# ihc_mon_orig.net
KiCad netlist of a schematic drawn in EAGLE
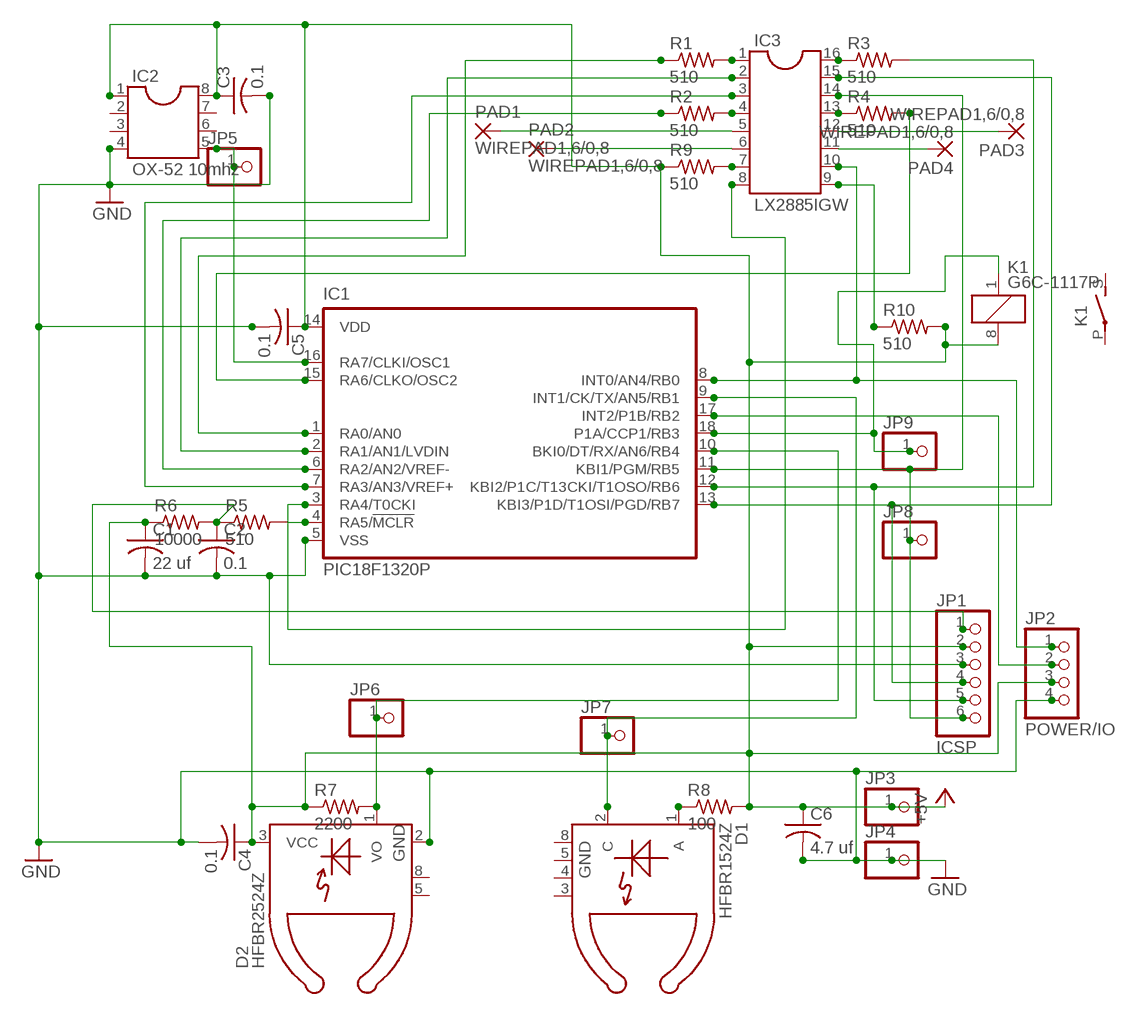
[diagram p0: schematic, sheet 1]

(export (version "E")
  (design (tool "Eeschema 10.0.6"))
  (components
    (comp (ref "C1")
      (value "22 uf")
      (footprint "eagle-import:C025-024X044")
      (libsource (lib "eagle-import") (part "C-US025-024X044"))
    )
    (comp (ref "C2")
      (value "0.1")
      (footprint "eagle-import:C050-025X075")
      (libsource (lib "eagle-import") (part "C-US050-025X075"))
    )
    (comp (ref "C3")
      (value "0.1")
      (footprint "eagle-import:C050-025X075")
      (libsource (lib "eagle-import") (part "C-US050-025X075"))
    )
    (comp (ref "C4")
      (value "0.1")
      (footprint "eagle-import:C050-025X075")
      (libsource (lib "eagle-import") (part "C-US050-025X075"))
    )
    (comp (ref "C5")
      (value "0.1")
      (footprint "eagle-import:C050-025X075")
      (libsource (lib "eagle-import") (part "C-US050-025X075"))
    )
    (comp (ref "C6")
      (value "4.7 uf")
      (footprint "eagle-import:C025-024X044")
      (libsource (lib "eagle-import") (part "C-US025-024X044"))
    )
    (comp (ref "D1")
      (value "HFBR1524Z")
      (footprint "eagle-import:HFBR25XX")
      (fields (field (name "MF") "AGILENT TECHNOLOGIES") (field (name "MPN") "HFBR-1528"))
      (libsource (lib "eagle-import") (part "HFBR1528"))
    )
    (comp (ref "D2")
      (value "HFBR2524Z")
      (footprint "eagle-import:HFBR25XX")
      (fields (field (name "MF") "AGILENT TECHNOLOGIES") (field (name "MPN") "HFBR-2528"))
      (libsource (lib "eagle-import") (part "HFBR2528"))
    )
    (comp (ref "IC1")
      (value "PIC18F1320P")
      (footprint "eagle-import:DIL18")
      (fields (field (name "MF") "MICROCHIP") (field (name "MPN") "PIC18F1320-I/P"))
      (libsource (lib "eagle-import") (part "PIC18F120P2"))
    )
    (comp (ref "IC2")
      (value "OX-52 10mhz")
      (footprint "eagle-import:SOCKET-08")
      (libsource (lib "eagle-import") (part "DIL8S"))
    )
    (comp (ref "IC3")
      (value "LX2885IGW")
      (footprint "eagle-import:SOCKET-16")
      (libsource (lib "eagle-import") (part "DIL16S"))
    )
    (comp (ref "JP1")
      (value "ICSP")
      (footprint "eagle-import:1X06")
      (libsource (lib "eagle-import") (part "PINHD-1X6"))
    )
    (comp (ref "JP2")
      (value "POWER/IO")
      (footprint "eagle-import:1X04")
      (libsource (lib "eagle-import") (part "PINHD-1X4"))
    )
    (comp (ref "JP3")
      (value "PINHD-1X1")
      (footprint "eagle-import:1X01")
      (libsource (lib "eagle-import") (part "PINHD-1X1"))
    )
    (comp (ref "JP4")
      (value "PINHD-1X1")
      (footprint "eagle-import:1X01")
      (libsource (lib "eagle-import") (part "PINHD-1X1"))
    )
    (comp (ref "JP5")
      (value "PINHD-1X1")
      (footprint "eagle-import:1X01")
      (libsource (lib "eagle-import") (part "PINHD-1X1"))
    )
    (comp (ref "JP6")
      (value "PINHD-1X1")
      (footprint "eagle-import:1X01")
      (libsource (lib "eagle-import") (part "PINHD-1X1"))
    )
    (comp (ref "JP7")
      (value "PINHD-1X1")
      (footprint "eagle-import:1X01")
      (libsource (lib "eagle-import") (part "PINHD-1X1"))
    )
    (comp (ref "JP8")
      (value "PINHD-1X1")
      (footprint "eagle-import:1X01")
      (libsource (lib "eagle-import") (part "PINHD-1X1"))
    )
    (comp (ref "JP9")
      (value "PINHD-1X1")
      (footprint "eagle-import:1X01")
      (libsource (lib "eagle-import") (part "PINHD-1X1"))
    )
    (comp (ref "K1")
      (value "G6C-1117P")
      (footprint "eagle-import:G6C-1117P")
      (libsource (lib "eagle-import") (part "G6C-1117P"))
    )
    (comp (ref "PAD1")
      (value "WIREPAD1,6/0,8")
      (footprint "eagle-import:1,6_0,8")
      (libsource (lib "eagle-import") (part "WIREPAD1,6/0,8"))
    )
    (comp (ref "PAD2")
      (value "WIREPAD1,6/0,8")
      (footprint "eagle-import:1,6_0,8")
      (libsource (lib "eagle-import") (part "WIREPAD1,6/0,8"))
    )
    (comp (ref "PAD3")
      (value "WIREPAD1,6/0,8")
      (footprint "eagle-import:1,6_0,8")
      (libsource (lib "eagle-import") (part "WIREPAD1,6/0,8"))
    )
    (comp (ref "PAD4")
      (value "WIREPAD1,6/0,8")
      (footprint "eagle-import:1,6_0,8")
      (libsource (lib "eagle-import") (part "WIREPAD1,6/0,8"))
    )
    (comp (ref "R1")
      (value "510")
      (footprint "eagle-import:0204V")
      (libsource (lib "eagle-import") (part "R-US_0204/2V"))
    )
    (comp (ref "R2")
      (value "510")
      (footprint "eagle-import:0204V")
      (libsource (lib "eagle-import") (part "R-US_0204/2V"))
    )
    (comp (ref "R3")
      (value "510")
      (footprint "eagle-import:0204V")
      (libsource (lib "eagle-import") (part "R-US_0204/2V"))
    )
    (comp (ref "R4")
      (value "510")
      (footprint "eagle-import:0204V")
      (libsource (lib "eagle-import") (part "R-US_0204/2V"))
    )
    (comp (ref "R5")
      (value "510")
      (footprint "eagle-import:0204V")
      (libsource (lib "eagle-import") (part "R-US_0204/2V"))
    )
    (comp (ref "R6")
      (value "10000")
      (footprint "eagle-import:0204V")
      (libsource (lib "eagle-import") (part "R-US_0204/2V"))
    )
    (comp (ref "R7")
      (value "2200")
      (footprint "eagle-import:0204V")
      (libsource (lib "eagle-import") (part "R-US_0204/2V"))
    )
    (comp (ref "R8")
      (value "100")
      (footprint "eagle-import:0204V")
      (libsource (lib "eagle-import") (part "R-US_0204/2V"))
    )
    (comp (ref "R9")
      (value "510")
      (footprint "eagle-import:0204V")
      (libsource (lib "eagle-import") (part "R-US_0204/2V"))
    )
    (comp (ref "R10")
      (value "510")
      (footprint "eagle-import:0204V")
      (libsource (lib "eagle-import") (part "R-US_0204/2V"))
    )
  )
  (nets
    (net (code "1") (name "+5V") (class "Default")
      (node (ref "C1") (pin "1") (pinfunction "1_1") (pintype "passive"))
      (node (ref "C3") (pin "1") (pinfunction "1_1") (pintype "passive"))
      (node (ref "C4") (pin "1") (pinfunction "1_1") (pintype "passive"))
      (node (ref "C5") (pin "1") (pinfunction "1_1") (pintype "passive"))
      (node (ref "C6") (pin "1") (pinfunction "1_1") (pintype "passive"))
      (node (ref "D2") (pin "3") (pinfunction "VCC_3") (pintype "passive"))
      (node (ref "IC1") (pin "14") (pinfunction "VDD_14") (pintype "power_in"))
      (node (ref "IC2") (pin "1") (pinfunction "1_1") (pintype "passive"))
      (node (ref "IC2") (pin "8") (pinfunction "8_8") (pintype "passive"))
      (node (ref "JP1") (pin "2") (pinfunction "2_2") (pintype "passive"))
      (node (ref "JP2") (pin "3") (pinfunction "3_3") (pintype "passive"))
      (node (ref "JP3") (pin "1") (pinfunction "1_1") (pintype "passive"))
      (node (ref "K1") (pin "8") (pinfunction "2_8") (pintype "passive"))
      (node (ref "R10") (pin "2") (pinfunction "2_2") (pintype "passive"))
      (node (ref "R6") (pin "1") (pinfunction "1_1") (pintype "passive"))
      (node (ref "R7") (pin "1") (pinfunction "1_1") (pintype "passive"))
      (node (ref "R8") (pin "2") (pinfunction "2_2") (pintype "passive"))
      (node (ref "R9") (pin "1") (pinfunction "1_1") (pintype "passive"))
    )
    (net (code "2") (name "GND") (class "Default")
      (node (ref "C1") (pin "2") (pinfunction "2_2") (pintype "passive"))
      (node (ref "C2") (pin "2") (pinfunction "2_2") (pintype "passive"))
      (node (ref "C3") (pin "2") (pinfunction "2_2") (pintype "passive"))
      (node (ref "C4") (pin "2") (pinfunction "2_2") (pintype "passive"))
      (node (ref "C5") (pin "2") (pinfunction "2_2") (pintype "passive"))
      (node (ref "C6") (pin "2") (pinfunction "2_2") (pintype "passive"))
      (node (ref "D2") (pin "2") (pinfunction "GND_2") (pintype "passive"))
      (node (ref "IC1") (pin "5") (pinfunction "VSS_5") (pintype "power_in"))
      (node (ref "IC2") (pin "4") (pinfunction "4_4") (pintype "passive"))
      (node (ref "JP1") (pin "3") (pinfunction "3_3") (pintype "passive"))
      (node (ref "JP2") (pin "4") (pinfunction "4_4") (pintype "passive"))
      (node (ref "JP4") (pin "1") (pinfunction "1_1") (pintype "passive"))
    )
    (net (code "3") (name "Net-(C2-Pad1)") (class "Default")
      (node (ref "C2") (pin "1") (pinfunction "1_1") (pintype "passive"))
      (node (ref "JP1") (pin "1") (pinfunction "1_1") (pintype "passive"))
      (node (ref "R5") (pin "1") (pinfunction "1_1") (pintype "passive"))
      (node (ref "R6") (pin "2") (pinfunction "2_2") (pintype "passive"))
    )
    (net (code "4") (name "Net-(D1-A)") (class "Default")
      (node (ref "D1") (pin "1") (pinfunction "A_1") (pintype "passive"))
      (node (ref "R8") (pin "1") (pinfunction "1_1") (pintype "passive"))
    )
    (net (code "5") (name "Net-(D1-C)") (class "Default")
      (node (ref "D1") (pin "2") (pinfunction "C_2") (pintype "passive"))
      (node (ref "IC1") (pin "9") (pinfunction "INT1/CK/TX/AN5/RB1_9") (pintype "bidirectional"))
      (node (ref "JP7") (pin "1") (pinfunction "1_1") (pintype "passive"))
    )
    (net (code "6") (name "Net-(D2-VO)") (class "Default")
      (node (ref "D2") (pin "1") (pinfunction "VO_1") (pintype "output"))
      (node (ref "IC1") (pin "10") (pinfunction "BKI0/DT/RX/AN6/RB4_10") (pintype "bidirectional"))
      (node (ref "JP6") (pin "1") (pinfunction "1_1") (pintype "passive"))
      (node (ref "R7") (pin "2") (pinfunction "2_2") (pintype "passive"))
    )
    (net (code "7") (name "Net-(IC1-INT0{slash}AN4{slash}RB0)") (class "Default")
      (node (ref "IC1") (pin "8") (pinfunction "INT0/AN4/RB0_8") (pintype "bidirectional"))
      (node (ref "IC3") (pin "10") (pinfunction "10_10") (pintype "passive"))
      (node (ref "JP2") (pin "1") (pinfunction "1_1") (pintype "passive"))
    )
    (net (code "8") (name "Net-(IC1-INT2{slash}P1B{slash}RB2)") (class "Default")
      (node (ref "IC1") (pin "17") (pinfunction "INT2/P1B/RB2_17") (pintype "bidirectional"))
      (node (ref "JP2") (pin "2") (pinfunction "2_2") (pintype "passive"))
    )
    (net (code "9") (name "Net-(IC1-KBI1{slash}PGM{slash}RB5)") (class "Default")
      (node (ref "IC1") (pin "11") (pinfunction "KBI1/PGM/RB5_11") (pintype "bidirectional"))
      (node (ref "IC3") (pin "14") (pinfunction "14_14") (pintype "passive"))
      (node (ref "JP1") (pin "6") (pinfunction "6_6") (pintype "passive"))
      (node (ref "JP8") (pin "1") (pinfunction "1_1") (pintype "passive"))
    )
    (net (code "10") (name "Net-(IC1-KBI2{slash}P1C{slash}T13CKI{slash}T1OSO{slash}RB6)") (class "Default")
      (node (ref "IC1") (pin "12") (pinfunction "KBI2/P1C/T13CKI/T1OSO/RB6_12") (pintype "bidirectional"))
      (node (ref "JP1") (pin "5") (pinfunction "5_5") (pintype "passive"))
      (node (ref "R3") (pin "2") (pinfunction "2_2") (pintype "passive"))
    )
    (net (code "11") (name "Net-(IC1-KBI3{slash}P1D{slash}T1OSI{slash}PGD{slash}RB7)") (class "Default")
      (node (ref "IC1") (pin "13") (pinfunction "KBI3/P1D/T1OSI/PGD/RB7_13") (pintype "bidirectional"))
      (node (ref "IC3") (pin "15") (pinfunction "15_15") (pintype "passive"))
      (node (ref "JP1") (pin "4") (pinfunction "4_4") (pintype "passive"))
    )
    (net (code "12") (name "Net-(IC1-P1A{slash}CCP1{slash}RB3)") (class "Default")
      (node (ref "IC1") (pin "18") (pinfunction "P1A/CCP1/RB3_18") (pintype "bidirectional"))
      (node (ref "JP9") (pin "1") (pinfunction "1_1") (pintype "passive"))
      (node (ref "K1") (pin "1") (pinfunction "1_1") (pintype "passive"))
    )
    (net (code "13") (name "Net-(IC1-RA0{slash}AN0)") (class "Default")
      (node (ref "IC1") (pin "1") (pinfunction "RA0/AN0_1") (pintype "bidirectional"))
      (node (ref "R1") (pin "1") (pinfunction "1_1") (pintype "passive"))
    )
    (net (code "14") (name "Net-(IC1-RA1{slash}AN1{slash}LVDIN)") (class "Default")
      (node (ref "IC1") (pin "2") (pinfunction "RA1/AN1/LVDIN_2") (pintype "bidirectional"))
      (node (ref "IC3") (pin "2") (pinfunction "2_2") (pintype "passive"))
    )
    (net (code "15") (name "Net-(IC1-RA2{slash}AN2{slash}VREF-)") (class "Default")
      (node (ref "IC1") (pin "6") (pinfunction "RA2/AN2/VREF-_6") (pintype "bidirectional"))
      (node (ref "R2") (pin "1") (pinfunction "1_1") (pintype "passive"))
    )
    (net (code "16") (name "Net-(IC1-RA3{slash}AN3{slash}VREF+)") (class "Default")
      (node (ref "IC1") (pin "7") (pinfunction "RA3/AN3/VREF+_7") (pintype "bidirectional"))
      (node (ref "IC3") (pin "3") (pinfunction "3_3") (pintype "passive"))
    )
    (net (code "17") (name "Net-(IC1-RA4{slash}T0CKI)") (class "Default")
      (node (ref "IC1") (pin "3") (pinfunction "RA4/T0CKI_3") (pintype "bidirectional"))
      (node (ref "IC3") (pin "8") (pinfunction "8_8") (pintype "passive"))
    )
    (net (code "18") (name "Net-(IC1-RA5{slash}~{MCLR})") (class "Default")
      (node (ref "IC1") (pin "4") (pinfunction "RA5/~{MCLR}_4") (pintype "input"))
      (node (ref "R5") (pin "2") (pinfunction "2_2") (pintype "passive"))
    )
    (net (code "19") (name "Net-(IC1-RA6{slash}CLKO{slash}OSC2)") (class "Default")
      (node (ref "IC1") (pin "15") (pinfunction "RA6/CLKO/OSC2_15") (pintype "bidirectional"))
      (node (ref "R4") (pin "2") (pinfunction "2_2") (pintype "passive"))
    )
    (net (code "20") (name "Net-(IC1-RA7{slash}CLKI{slash}OSC1)") (class "Default")
      (node (ref "IC1") (pin "16") (pinfunction "RA7/CLKI/OSC1_16") (pintype "bidirectional"))
      (node (ref "IC2") (pin "5") (pinfunction "5_5") (pintype "passive"))
      (node (ref "JP5") (pin "1") (pinfunction "1_1") (pintype "passive"))
    )
    (net (code "21") (name "Net-(IC3-Pad1)") (class "Default")
      (node (ref "IC3") (pin "1") (pinfunction "1_1") (pintype "passive"))
      (node (ref "R1") (pin "2") (pinfunction "2_2") (pintype "passive"))
    )
    (net (code "22") (name "Net-(IC3-Pad4)") (class "Default")
      (node (ref "IC3") (pin "4") (pinfunction "4_4") (pintype "passive"))
      (node (ref "R2") (pin "2") (pinfunction "2_2") (pintype "passive"))
    )
    (net (code "23") (name "Net-(IC3-Pad7)") (class "Default")
      (node (ref "IC3") (pin "7") (pinfunction "7_7") (pintype "passive"))
      (node (ref "R9") (pin "2") (pinfunction "2_2") (pintype "passive"))
    )
    (net (code "24") (name "Net-(IC3-Pad9)") (class "Default")
      (node (ref "IC3") (pin "9") (pinfunction "9_9") (pintype "passive"))
      (node (ref "R10") (pin "1") (pinfunction "1_1") (pintype "passive"))
    )
    (net (code "25") (name "Net-(IC3-Pad13)") (class "Default")
      (node (ref "IC3") (pin "13") (pinfunction "13_13") (pintype "passive"))
      (node (ref "R4") (pin "1") (pinfunction "1_1") (pintype "passive"))
    )
    (net (code "26") (name "Net-(IC3-Pad16)") (class "Default")
      (node (ref "IC3") (pin "16") (pinfunction "16_16") (pintype "passive"))
      (node (ref "R3") (pin "1") (pinfunction "1_1") (pintype "passive"))
    )
    (net (code "27") (name "Net-(PAD1-P)") (class "Default")
      (node (ref "IC3") (pin "5") (pinfunction "5_5") (pintype "passive"))
      (node (ref "PAD1") (pin "1") (pinfunction "P_1") (pintype "passive"))
    )
    (net (code "28") (name "Net-(PAD2-P)") (class "Default")
      (node (ref "IC3") (pin "6") (pinfunction "6_6") (pintype "passive"))
      (node (ref "PAD2") (pin "1") (pinfunction "P_1") (pintype "passive"))
    )
    (net (code "29") (name "Net-(PAD3-P)") (class "Default")
      (node (ref "IC3") (pin "12") (pinfunction "12_12") (pintype "passive"))
      (node (ref "PAD3") (pin "1") (pinfunction "P_1") (pintype "passive"))
    )
    (net (code "30") (name "Net-(PAD4-P)") (class "Default")
      (node (ref "IC3") (pin "11") (pinfunction "11_11") (pintype "passive"))
      (node (ref "PAD4") (pin "1") (pinfunction "P_1") (pintype "passive"))
    )
    (net (code "31") (name "unconnected-(D1-1-Pad3)") (class "Default")
      (node (ref "D1") (pin "3") (pinfunction "1_3") (pintype "passive"))
    )
    (net (code "32") (name "unconnected-(D1-GND-Pad5)") (class "Default")
      (node (ref "D1") (pin "5") (pinfunction "GND_5") (pintype "passive"))
    )
    (net (code "33") (name "unconnected-(D1-GND-Pad8)") (class "Default")
      (node (ref "D1") (pin "8") (pinfunction "GND_8") (pintype "passive"))
    )
    (net (code "34") (name "unconnected-(D1-Pad4)") (class "Default")
      (node (ref "D1") (pin "4") (pinfunction "4_4") (pintype "passive"))
    )
    (net (code "35") (name "unconnected-(D2-1-Pad5)") (class "Default")
      (node (ref "D2") (pin "5") (pinfunction "1_5") (pintype "passive"))
    )
    (net (code "36") (name "unconnected-(D2-4-Pad8)") (class "Default")
      (node (ref "D2") (pin "8") (pinfunction "4_8") (pintype "passive"))
    )
    (net (code "37") (name "unconnected-(IC2-Pad2)") (class "Default")
      (node (ref "IC2") (pin "2") (pinfunction "2_2") (pintype "passive"))
    )
    (net (code "38") (name "unconnected-(IC2-Pad3)") (class "Default")
      (node (ref "IC2") (pin "3") (pinfunction "3_3") (pintype "passive"))
    )
    (net (code "39") (name "unconnected-(IC2-Pad6)") (class "Default")
      (node (ref "IC2") (pin "6") (pinfunction "6_6") (pintype "passive"))
    )
    (net (code "40") (name "unconnected-(IC2-Pad7)") (class "Default")
      (node (ref "IC2") (pin "7") (pinfunction "7_7") (pintype "passive"))
    )
    (net (code "41") (name "unconnected-(K1-PadP)") (class "Default")
      (node (ref "K1") (pin "P") (pinfunction "P_P") (pintype "passive"))
    )
    (net (code "42") (name "unconnected-(K1-PadS)") (class "Default")
      (node (ref "K1") (pin "S") (pinfunction "S_S") (pintype "passive"))
    )
  )
)
